# PWR_N5V0A.net
KiCad netlist of a schematic drawn in Altium Designer
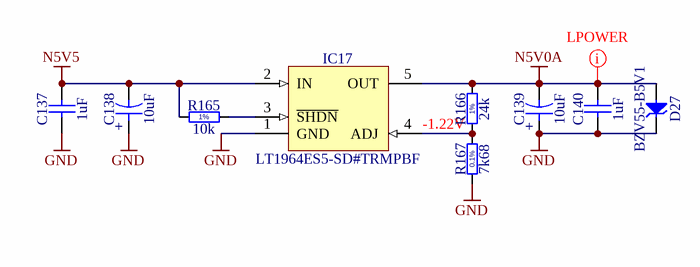
[diagram p0: PWR_N5V0A.SchDoc]

(export (version "E")
  (design (tool "Eeschema 10.0.6"))
  (components
    (comp (ref "C137")
      (value "1uF")
      (footprint "CAPC1005X55N")
      (description "Non-polarised capacitor")
      (fields
        (field (name "PART NUMBER") "CC0402_1UF_16V_10%_X5R")
        (field (name "VOLTAGE") "16V")
        (field (name "AUTHOR") "CERN DEM JLC")
      )
      (libsource (lib "Capacitors") (part "Capacitor - non polarized"))
    )
    (comp (ref "C138")
      (value "10uF")
      (footprint "CAPMP3216X180N")
      (description "Polarised capacitor")
      (fields
        (field (name "PART NUMBER") "CTE3216-18_10UF_16V_20%_AVX_TCJ")
        (field (name "VOLTAGE") "16V")
        (field (name "AUTHOR") "CERN DEM JLC")
      )
      (libsource (lib "Capacitors") (part "Capacitor - polarized"))
    )
    (comp (ref "C139")
      (value "10uF")
      (footprint "CAPMP3216X180N")
      (description "Polarised capacitor")
      (fields
        (field (name "PART NUMBER") "CTE3216-18_10UF_16V_20%_AVX_TCJ")
        (field (name "VOLTAGE") "16V")
        (field (name "AUTHOR") "CERN DEM JLC")
      )
      (libsource (lib "Capacitors") (part "Capacitor - polarized"))
    )
    (comp (ref "C140")
      (value "1uF")
      (footprint "CAPC1005X55N")
      (description "Non-polarised capacitor")
      (fields
        (field (name "PART NUMBER") "CC0402_1UF_16V_10%_X5R")
        (field (name "VOLTAGE") "16V")
        (field (name "AUTHOR") "CERN DEM JLC")
      )
      (libsource (lib "Capacitors") (part "Capacitor - non polarized"))
    )
    (comp (ref "D27")
      (value "BZV55-B5V1")
      (footprint "DIOMELF3515N")
      (description "Zener Diode")
      (fields
        (field (name "VOLTAGE") "5V1")
        (field (name "POWER") "500mW")
        (field (name "AUTHOR") "CERN DEM JLC")
      )
      (libsource (lib "ICs And Semiconductors") (part "Diode Zener"))
    )
    (comp (ref "IC17")
      (value "LT1964ES5-SD#TRMPBF")
      (footprint "SOT95P280X100-5N")
      (description "200mA, Low Noise, Low Dropout Negative Micropower Regulator")
      (fields (field (name "MANUFACTURER") "LINEAR TECHNOLOGY") (field (name "AUTHOR") "CERN DEM JLC"))
      (libsource (lib "ICs And Semiconductors") (part "LT1964-SD"))
    )
    (comp (ref "R165")
      (value "10k")
      (footprint "RESC1005X40N")
      (description "Resistor - 1%")
      (fields
        (field (name "PART NUMBER") "R0402_10K_1%_0.0625W_100PPM")
        (field (name "MANUFACTURER") "GENERIC")
        (field (name "AUTHOR") "CERN DEM JLC")
      )
      (libsource (lib "Resistors") (part "Resistor - 1%"))
    )
    (comp (ref "R166")
      (value "24k")
      (footprint "RESC1608X55N")
      (description "Resistor - 1%")
      (fields
        (field (name "PART NUMBER") "R0603_24K_1%_0.1W_100PPM")
        (field (name "POWER") "0.1W")
        (field (name "AUTHOR") "CERN DEM JLC")
      )
      (libsource (lib "Resistors") (part "Resistor - 1%"))
    )
    (comp (ref "R167")
      (value "7k68")
      (footprint "RESC1608X55N")
      (description "Resistor - 0.1%")
      (fields
        (field (name "PART NUMBER") "R0603_7K68_0.1%_0.063W_10PPM")
        (field (name "POWER") "0.063W")
        (field (name "AUTHOR") "CERN DEM JLC")
      )
      (libsource (lib "Resistors") (part "Resistor - 0.1%"))
    )
  )
  (nets
    (net (code "1") (name "GND") (class "Default")
      (node (ref "C137") (pin "1") (pinfunction "1_1") (pintype "passive"))
      (node (ref "C138") (pin "1") (pinfunction "1_1") (pintype "passive"))
      (node (ref "C139") (pin "1") (pinfunction "1_1") (pintype "passive"))
      (node (ref "C140") (pin "1") (pinfunction "1_1") (pintype "passive"))
      (node (ref "D27") (pin "1") (pinfunction "C_1") (pintype "passive"))
      (node (ref "IC17") (pin "1") (pinfunction "GND_1") (pintype "power_in"))
      (node (ref "R167") (pin "1") (pinfunction "1_1") (pintype "passive"))
    )
    (net (code "2") (name "N5V0A") (class "Default")
      (node (ref "C139") (pin "2") (pinfunction "2_2") (pintype "passive"))
      (node (ref "C140") (pin "2") (pinfunction "2_2") (pintype "passive"))
      (node (ref "D27") (pin "2") (pinfunction "A_2") (pintype "passive"))
      (node (ref "IC17") (pin "5") (pinfunction "OUT_5") (pintype "power_in"))
      (node (ref "R166") (pin "2") (pinfunction "2_2") (pintype "passive"))
    )
    (net (code "3") (name "N5V5") (class "Default")
      (node (ref "C137") (pin "2") (pinfunction "2_2") (pintype "passive"))
      (node (ref "C138") (pin "2") (pinfunction "2_2") (pintype "passive"))
      (node (ref "IC17") (pin "2") (pinfunction "IN_2") (pintype "input"))
      (node (ref "R165") (pin "1") (pinfunction "1_1") (pintype "passive"))
    )
    (net (code "4") (name "Net-(IC17-ADJ)") (class "Default")
      (node (ref "IC17") (pin "4") (pinfunction "ADJ_4") (pintype "input"))
      (node (ref "R166") (pin "1") (pinfunction "1_1") (pintype "passive"))
      (node (ref "R167") (pin "2") (pinfunction "2_2") (pintype "passive"))
    )
    (net (code "5") (name "Net-(IC17-~{SHDN})") (class "Default")
      (node (ref "IC17") (pin "3") (pinfunction "~{SHDN}_3") (pintype "input"))
      (node (ref "R165") (pin "2") (pinfunction "2_2") (pintype "passive"))
    )
  )
)
